# SMTRelayController.net
KiCad netlist of a schematic drawn in EAGLE
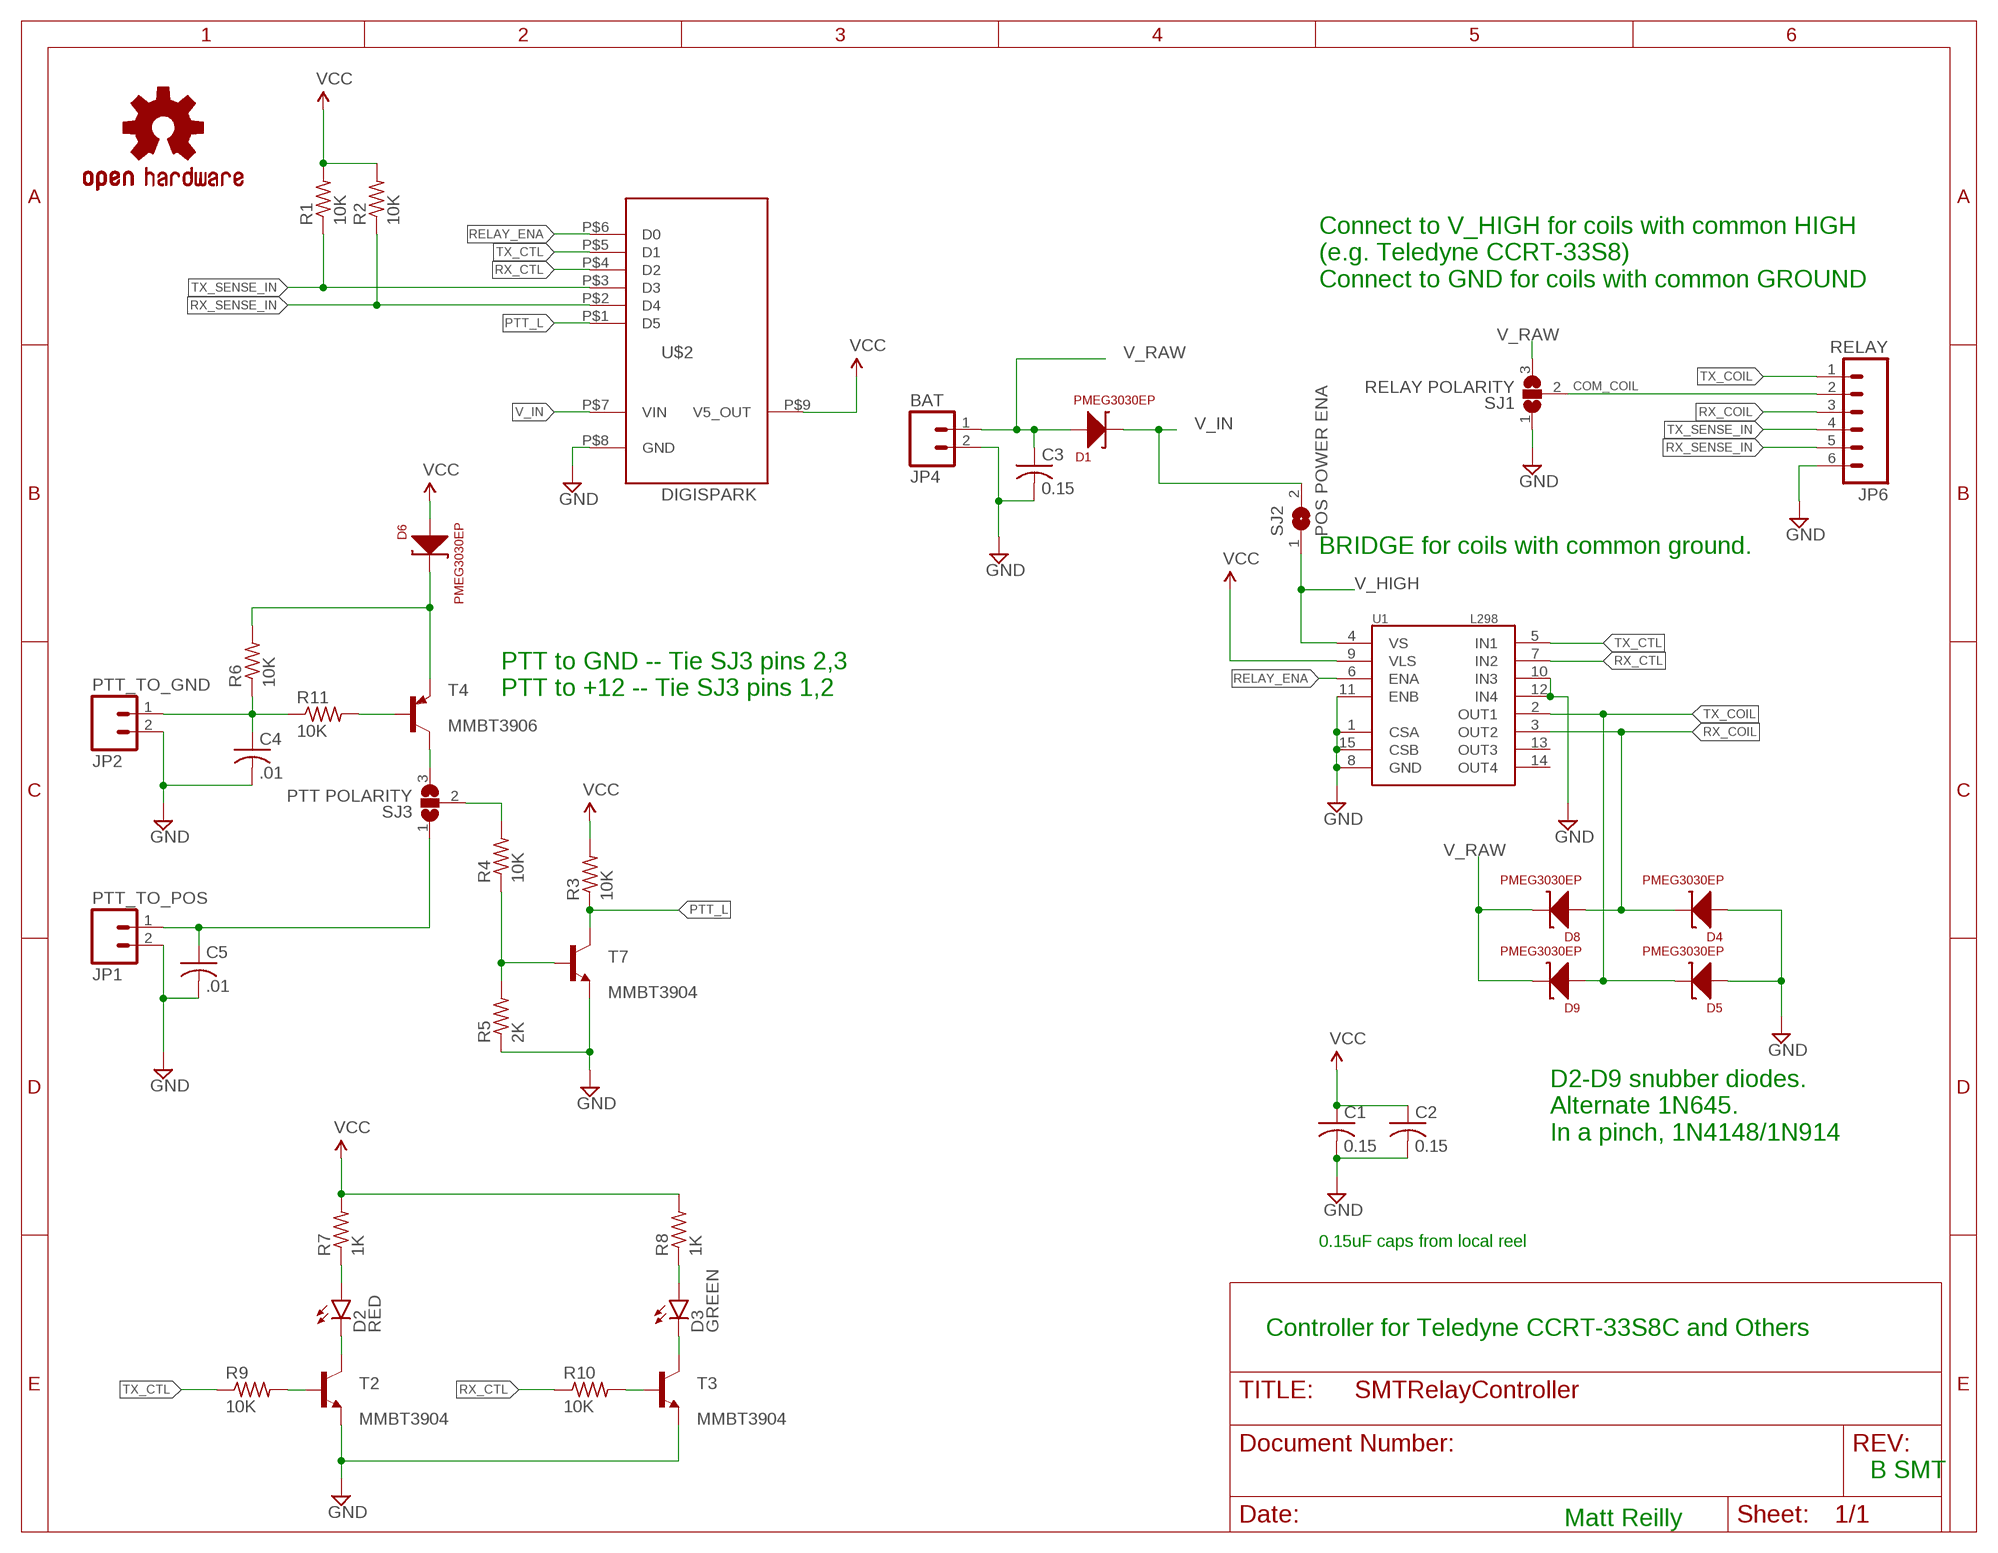
[diagram p0: schematic, sheet 1]

(export (version "E")
  (design (tool "Eeschema 10.0.6"))
  (components
    (comp (ref "C1")
      (value "0.15")
      (footprint "eagle-import:C1206K")
      (libsource (lib "eagle-import") (part "C-USC1206K"))
    )
    (comp (ref "C2")
      (value "0.15")
      (footprint "eagle-import:C1206K")
      (libsource (lib "eagle-import") (part "C-USC1206K"))
    )
    (comp (ref "C3")
      (value "0.15")
      (footprint "eagle-import:C1206K")
      (libsource (lib "eagle-import") (part "C-USC1206K"))
    )
    (comp (ref "C4")
      (value ".01")
      (footprint "eagle-import:C1206K")
      (libsource (lib "eagle-import") (part "C-USC1206K"))
    )
    (comp (ref "C5")
      (value ".01")
      (footprint "eagle-import:C1206K")
      (libsource (lib "eagle-import") (part "C-USC1206K"))
    )
    (comp (ref "D1")
      (value "PMEG3030EP")
      (footprint "eagle-import:SOD128")
      (libsource (lib "eagle-import") (part "PMEG3030EP"))
    )
    (comp (ref "D2")
      (value "RED")
      (footprint "eagle-import:LED-1206")
      (libsource (lib "eagle-import") (part "LED1206"))
    )
    (comp (ref "D3")
      (value "GREEN")
      (footprint "eagle-import:LED-1206")
      (libsource (lib "eagle-import") (part "LED1206"))
    )
    (comp (ref "D4")
      (value "PMEG3030EP")
      (footprint "eagle-import:SOD128")
      (libsource (lib "eagle-import") (part "PMEG3030EP"))
    )
    (comp (ref "D5")
      (value "PMEG3030EP")
      (footprint "eagle-import:SOD128")
      (libsource (lib "eagle-import") (part "PMEG3030EP"))
    )
    (comp (ref "D6")
      (value "PMEG3030EP")
      (footprint "eagle-import:SOD128")
      (libsource (lib "eagle-import") (part "PMEG3030EP"))
    )
    (comp (ref "D8")
      (value "PMEG3030EP")
      (footprint "eagle-import:SOD128")
      (libsource (lib "eagle-import") (part "PMEG3030EP"))
    )
    (comp (ref "D9")
      (value "PMEG3030EP")
      (footprint "eagle-import:SOD128")
      (libsource (lib "eagle-import") (part "PMEG3030EP"))
    )
    (comp (ref "JP1")
      (value "PTT_TO_POS")
      (footprint "eagle-import:SCREWTERMINAL-5MM-2")
      (libsource (lib "eagle-import") (part "M025MM"))
    )
    (comp (ref "JP2")
      (value "PTT_TO_GND")
      (footprint "eagle-import:SCREWTERMINAL-5MM-2")
      (libsource (lib "eagle-import") (part "M025MM"))
    )
    (comp (ref "JP4")
      (value "BAT")
      (footprint "eagle-import:SCREWTERMINAL-5MM-2")
      (libsource (lib "eagle-import") (part "M025MM"))
    )
    (comp (ref "JP6")
      (value "RELAY")
      (footprint "eagle-import:MOLEX-1X6")
      (libsource (lib "eagle-import") (part "M06POLAR"))
    )
    (comp (ref "LOGO1")
      (value "OSHW-LOGOM-COPPER")
      (footprint "eagle-import:OSHW-LOGO-M_COPPER")
      (libsource (lib "eagle-import") (part "OSHW-LOGOM-COPPER"))
    )
    (comp (ref "R1")
      (value "10K")
      (footprint "eagle-import:R1206")
      (libsource (lib "eagle-import") (part "R-US_R1206"))
    )
    (comp (ref "R2")
      (value "10K")
      (footprint "eagle-import:R1206")
      (libsource (lib "eagle-import") (part "R-US_R1206"))
    )
    (comp (ref "R3")
      (value "10K")
      (footprint "eagle-import:R1206")
      (libsource (lib "eagle-import") (part "R-US_R1206"))
    )
    (comp (ref "R4")
      (value "10K")
      (footprint "eagle-import:R1206")
      (libsource (lib "eagle-import") (part "R-US_R1206"))
    )
    (comp (ref "R5")
      (value "2K")
      (footprint "eagle-import:R1206")
      (libsource (lib "eagle-import") (part "R-US_R1206"))
    )
    (comp (ref "R6")
      (value "10K")
      (footprint "eagle-import:R1206")
      (libsource (lib "eagle-import") (part "R-US_R1206"))
    )
    (comp (ref "R7")
      (value "1K")
      (footprint "eagle-import:R1206")
      (libsource (lib "eagle-import") (part "R-US_R1206"))
    )
    (comp (ref "R8")
      (value "1K")
      (footprint "eagle-import:R1206")
      (libsource (lib "eagle-import") (part "R-US_R1206"))
    )
    (comp (ref "R9")
      (value "10K")
      (footprint "eagle-import:R1206")
      (libsource (lib "eagle-import") (part "R-US_R1206"))
    )
    (comp (ref "R10")
      (value "10K")
      (footprint "eagle-import:R1206")
      (libsource (lib "eagle-import") (part "R-US_R1206"))
    )
    (comp (ref "R11")
      (value "10K")
      (footprint "eagle-import:R1206")
      (libsource (lib "eagle-import") (part "R-US_R1206"))
    )
    (comp (ref "SJ1")
      (value "RELAY POLARITY")
      (footprint "eagle-import:SJ_2W")
      (libsource (lib "eagle-import") (part "SJ2WW"))
    )
    (comp (ref "SJ2")
      (value "POS POWER ENA")
      (footprint "eagle-import:SJW")
      (libsource (lib "eagle-import") (part "SJW"))
    )
    (comp (ref "SJ3")
      (value "PTT POLARITY")
      (footprint "eagle-import:SJ_2W")
      (libsource (lib "eagle-import") (part "SJ2WW"))
    )
    (comp (ref "T2")
      (value "MMBT3904")
      (footprint "eagle-import:SOT23-BEC")
      (libsource (lib "eagle-import") (part "-NPN-SOT23-BECMMBT3904LT1"))
    )
    (comp (ref "T3")
      (value "MMBT3904")
      (footprint "eagle-import:SOT23-BEC")
      (libsource (lib "eagle-import") (part "-NPN-SOT23-BECMMBT3904LT1"))
    )
    (comp (ref "T4")
      (value "MMBT3906")
      (footprint "eagle-import:SOT23-BEC")
      (libsource (lib "eagle-import") (part "-PNP-SOT23-BECMMBT3906LT1"))
    )
    (comp (ref "T7")
      (value "MMBT3904")
      (footprint "eagle-import:SOT23-BEC")
      (libsource (lib "eagle-import") (part "-NPN-SOT23-BECMMBT3904LT1"))
    )
    (comp (ref "U$2")
      (value "DIGISPARK")
      (footprint "eagle-import:DIGISPARK_FP")
      (libsource (lib "eagle-import") (part "DIGISPARK"))
    )
    (comp (ref "U1")
      (value "L298")
      (footprint "eagle-import:MULTIWATT15")
      (libsource (lib "eagle-import") (part "L298"))
    )
  )
  (nets
    (net (code "1") (name "/COM_COIL") (class "Default")
      (node (ref "JP6") (pin "2") (pinfunction "2_2") (pintype "passive"))
      (node (ref "SJ1") (pin "2") (pinfunction "2_2") (pintype "passive"))
    )
    (net (code "2") (name "/V_HIGH") (class "Default")
      (node (ref "SJ2") (pin "1") (pinfunction "1_1") (pintype "passive"))
      (node (ref "U1") (pin "4") (pinfunction "VS_4") (pintype "bidirectional"))
    )
    (net (code "3") (name "/V_RAW") (class "Default")
      (node (ref "C3") (pin "1") (pinfunction "1_1") (pintype "passive"))
      (node (ref "D1") (pin "P$1") (pinfunction "A_P$1") (pintype "bidirectional"))
      (node (ref "D8") (pin "P$2") (pinfunction "C_P$2") (pintype "bidirectional"))
      (node (ref "D9") (pin "P$2") (pinfunction "C_P$2") (pintype "bidirectional"))
      (node (ref "JP4") (pin "1") (pinfunction "1_1") (pintype "passive"))
      (node (ref "SJ1") (pin "3") (pinfunction "3_3") (pintype "passive"))
    )
    (net (code "4") (name "GND") (class "Default")
      (node (ref "C1") (pin "2") (pinfunction "2_2") (pintype "passive"))
      (node (ref "C2") (pin "2") (pinfunction "2_2") (pintype "passive"))
      (node (ref "C3") (pin "2") (pinfunction "2_2") (pintype "passive"))
      (node (ref "C4") (pin "2") (pinfunction "2_2") (pintype "passive"))
      (node (ref "C5") (pin "2") (pinfunction "2_2") (pintype "passive"))
      (node (ref "D4") (pin "P$1") (pinfunction "A_P$1") (pintype "bidirectional"))
      (node (ref "D5") (pin "P$1") (pinfunction "A_P$1") (pintype "bidirectional"))
      (node (ref "JP1") (pin "2") (pinfunction "2_2") (pintype "passive"))
      (node (ref "JP2") (pin "2") (pinfunction "2_2") (pintype "passive"))
      (node (ref "JP4") (pin "2") (pinfunction "2_2") (pintype "passive"))
      (node (ref "JP6") (pin "6") (pinfunction "6_6") (pintype "passive"))
      (node (ref "R5") (pin "1") (pinfunction "1_1") (pintype "passive"))
      (node (ref "SJ1") (pin "1") (pinfunction "1_1") (pintype "passive"))
      (node (ref "T2") (pin "E") (pinfunction "E_E") (pintype "passive"))
      (node (ref "T3") (pin "E") (pinfunction "E_E") (pintype "passive"))
      (node (ref "T7") (pin "E") (pinfunction "E_E") (pintype "passive"))
      (node (ref "U$2") (pin "P$8") (pinfunction "GND_P$8") (pintype "bidirectional"))
      (node (ref "U1") (pin "1") (pinfunction "CSA_1") (pintype "bidirectional"))
      (node (ref "U1") (pin "10") (pinfunction "IN3_10") (pintype "bidirectional"))
      (node (ref "U1") (pin "11") (pinfunction "ENB_11") (pintype "bidirectional"))
      (node (ref "U1") (pin "12") (pinfunction "IN4_12") (pintype "bidirectional"))
      (node (ref "U1") (pin "15") (pinfunction "CSB_15") (pintype "bidirectional"))
      (node (ref "U1") (pin "8") (pinfunction "GND_8") (pintype "bidirectional"))
    )
    (net (code "5") (name "Net-(C4-Pad1)") (class "Default")
      (node (ref "C4") (pin "1") (pinfunction "1_1") (pintype "passive"))
      (node (ref "JP2") (pin "1") (pinfunction "1_1") (pintype "passive"))
      (node (ref "R11") (pin "1") (pinfunction "1_1") (pintype "passive"))
      (node (ref "R6") (pin "1") (pinfunction "1_1") (pintype "passive"))
    )
    (net (code "6") (name "Net-(C5-Pad1)") (class "Default")
      (node (ref "C5") (pin "1") (pinfunction "1_1") (pintype "passive"))
      (node (ref "JP1") (pin "1") (pinfunction "1_1") (pintype "passive"))
      (node (ref "SJ3") (pin "1") (pinfunction "1_1") (pintype "passive"))
    )
    (net (code "7") (name "Net-(D2-PadA)") (class "Default")
      (node (ref "D2") (pin "A") (pinfunction "A_A") (pintype "passive"))
      (node (ref "R7") (pin "1") (pinfunction "1_1") (pintype "passive"))
    )
    (net (code "8") (name "Net-(D2-PadC)") (class "Default")
      (node (ref "D2") (pin "C") (pinfunction "C_C") (pintype "passive"))
      (node (ref "T2") (pin "C") (pinfunction "C_C") (pintype "passive"))
    )
    (net (code "9") (name "Net-(D3-PadA)") (class "Default")
      (node (ref "D3") (pin "A") (pinfunction "A_A") (pintype "passive"))
      (node (ref "R8") (pin "1") (pinfunction "1_1") (pintype "passive"))
    )
    (net (code "10") (name "Net-(D3-PadC)") (class "Default")
      (node (ref "D3") (pin "C") (pinfunction "C_C") (pintype "passive"))
      (node (ref "T3") (pin "C") (pinfunction "C_C") (pintype "passive"))
    )
    (net (code "11") (name "Net-(D6-C)") (class "Default")
      (node (ref "D6") (pin "P$2") (pinfunction "C_P$2") (pintype "bidirectional"))
      (node (ref "R6") (pin "2") (pinfunction "2_2") (pintype "passive"))
      (node (ref "T4") (pin "E") (pinfunction "E_E") (pintype "passive"))
    )
    (net (code "12") (name "Net-(R4-Pad1)") (class "Default")
      (node (ref "R4") (pin "1") (pinfunction "1_1") (pintype "passive"))
      (node (ref "R5") (pin "2") (pinfunction "2_2") (pintype "passive"))
      (node (ref "T7") (pin "B") (pinfunction "B_B") (pintype "passive"))
    )
    (net (code "13") (name "Net-(R4-Pad2)") (class "Default")
      (node (ref "R4") (pin "2") (pinfunction "2_2") (pintype "passive"))
      (node (ref "SJ3") (pin "2") (pinfunction "2_2") (pintype "passive"))
    )
    (net (code "14") (name "Net-(R9-Pad2)") (class "Default")
      (node (ref "R9") (pin "2") (pinfunction "2_2") (pintype "passive"))
      (node (ref "T2") (pin "B") (pinfunction "B_B") (pintype "passive"))
    )
    (net (code "15") (name "Net-(R10-Pad2)") (class "Default")
      (node (ref "R10") (pin "2") (pinfunction "2_2") (pintype "passive"))
      (node (ref "T3") (pin "B") (pinfunction "B_B") (pintype "passive"))
    )
    (net (code "16") (name "Net-(R11-Pad2)") (class "Default")
      (node (ref "R11") (pin "2") (pinfunction "2_2") (pintype "passive"))
      (node (ref "T4") (pin "B") (pinfunction "B_B") (pintype "passive"))
    )
    (net (code "17") (name "Net-(SJ3-Pad3)") (class "Default")
      (node (ref "SJ3") (pin "3") (pinfunction "3_3") (pintype "passive"))
      (node (ref "T4") (pin "C") (pinfunction "C_C") (pintype "passive"))
    )
    (net (code "18") (name "PTT_L") (class "Default")
      (node (ref "R3") (pin "1") (pinfunction "1_1") (pintype "passive"))
      (node (ref "T7") (pin "C") (pinfunction "C_C") (pintype "passive"))
      (node (ref "U$2") (pin "P$1") (pinfunction "D5_P$1") (pintype "bidirectional"))
    )
    (net (code "19") (name "RELAY_ENA") (class "Default")
      (node (ref "U$2") (pin "P$6") (pinfunction "D0_P$6") (pintype "bidirectional"))
      (node (ref "U1") (pin "6") (pinfunction "ENA_6") (pintype "bidirectional"))
    )
    (net (code "20") (name "RX_COIL") (class "Default")
      (node (ref "D4") (pin "P$2") (pinfunction "C_P$2") (pintype "bidirectional"))
      (node (ref "D8") (pin "P$1") (pinfunction "A_P$1") (pintype "bidirectional"))
      (node (ref "JP6") (pin "3") (pinfunction "3_3") (pintype "passive"))
      (node (ref "U1") (pin "3") (pinfunction "OUT2_3") (pintype "bidirectional"))
    )
    (net (code "21") (name "RX_CTL") (class "Default")
      (node (ref "R10") (pin "1") (pinfunction "1_1") (pintype "passive"))
      (node (ref "U$2") (pin "P$4") (pinfunction "D2_P$4") (pintype "bidirectional"))
      (node (ref "U1") (pin "7") (pinfunction "IN2_7") (pintype "bidirectional"))
    )
    (net (code "22") (name "RX_SENSE_IN") (class "Default")
      (node (ref "JP6") (pin "5") (pinfunction "5_5") (pintype "passive"))
      (node (ref "R2") (pin "1") (pinfunction "1_1") (pintype "passive"))
      (node (ref "U$2") (pin "P$2") (pinfunction "D4_P$2") (pintype "bidirectional"))
    )
    (net (code "23") (name "TX_COIL") (class "Default")
      (node (ref "D5") (pin "P$2") (pinfunction "C_P$2") (pintype "bidirectional"))
      (node (ref "D9") (pin "P$1") (pinfunction "A_P$1") (pintype "bidirectional"))
      (node (ref "JP6") (pin "1") (pinfunction "1_1") (pintype "passive"))
      (node (ref "U1") (pin "2") (pinfunction "OUT1_2") (pintype "bidirectional"))
    )
    (net (code "24") (name "TX_CTL") (class "Default")
      (node (ref "R9") (pin "1") (pinfunction "1_1") (pintype "passive"))
      (node (ref "U$2") (pin "P$5") (pinfunction "D1_P$5") (pintype "bidirectional"))
      (node (ref "U1") (pin "5") (pinfunction "IN1_5") (pintype "bidirectional"))
    )
    (net (code "25") (name "TX_SENSE_IN") (class "Default")
      (node (ref "JP6") (pin "4") (pinfunction "4_4") (pintype "passive"))
      (node (ref "R1") (pin "1") (pinfunction "1_1") (pintype "passive"))
      (node (ref "U$2") (pin "P$3") (pinfunction "D3_P$3") (pintype "bidirectional"))
    )
    (net (code "26") (name "VCC") (class "Default")
      (node (ref "C1") (pin "1") (pinfunction "1_1") (pintype "passive"))
      (node (ref "C2") (pin "1") (pinfunction "1_1") (pintype "passive"))
      (node (ref "D6") (pin "P$1") (pinfunction "A_P$1") (pintype "bidirectional"))
      (node (ref "R1") (pin "2") (pinfunction "2_2") (pintype "passive"))
      (node (ref "R2") (pin "2") (pinfunction "2_2") (pintype "passive"))
      (node (ref "R3") (pin "2") (pinfunction "2_2") (pintype "passive"))
      (node (ref "R7") (pin "2") (pinfunction "2_2") (pintype "passive"))
      (node (ref "R8") (pin "2") (pinfunction "2_2") (pintype "passive"))
      (node (ref "U$2") (pin "P$9") (pinfunction "V5_OUT_P$9") (pintype "bidirectional"))
      (node (ref "U1") (pin "9") (pinfunction "VLS_9") (pintype "bidirectional"))
    )
    (net (code "27") (name "V_IN") (class "Default")
      (node (ref "D1") (pin "P$2") (pinfunction "C_P$2") (pintype "bidirectional"))
      (node (ref "SJ2") (pin "2") (pinfunction "2_2") (pintype "passive"))
      (node (ref "U$2") (pin "P$7") (pinfunction "VIN_P$7") (pintype "bidirectional"))
    )
    (net (code "28") (name "unconnected-(U1-OUT3-Pad13)") (class "Default")
      (node (ref "U1") (pin "13") (pinfunction "OUT3_13") (pintype "bidirectional"))
    )
    (net (code "29") (name "unconnected-(U1-OUT4-Pad14)") (class "Default")
      (node (ref "U1") (pin "14") (pinfunction "OUT4_14") (pintype "bidirectional"))
    )
  )
)
